# lcdconnector3.net
KiCad netlist of a schematic drawn in EAGLE
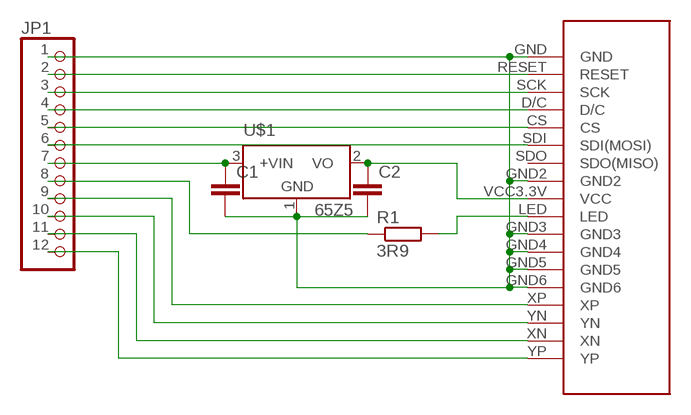
[diagram p0: schematic, sheet 1]

(export (version "E")
  (design (tool "Eeschema 10.0.6"))
  (components
    (comp (ref "C1")
      (value "C-EUC0805")
      (footprint "eagle-import:C0805")
      (libsource (lib "eagle-import") (part "C-EUC0805"))
    )
    (comp (ref "C2")
      (value "C-EUC0805")
      (footprint "eagle-import:C0805")
      (libsource (lib "eagle-import") (part "C-EUC0805"))
    )
    (comp (ref "CONNECTOR1")
      (value "TJCTM24024-PINS")
      (footprint "eagle-import:TJCTM24024-PINS")
      (libsource (lib "eagle-import") (part "TJCTM24024-PINS"))
    )
    (comp (ref "JP1")
      (value "PINHD-1X12-CB")
      (footprint "eagle-import:1X12-CB")
      (libsource (lib "eagle-import") (part "PINHD-1X12-CB"))
    )
    (comp (ref "R1")
      (value "3R9")
      (footprint "eagle-import:R0805")
      (libsource (lib "eagle-import") (part "R-EU_R0805"))
    )
    (comp (ref "U$1")
      (value "65Z5")
      (footprint "eagle-import:SOT23")
      (libsource (lib "eagle-import") (part "65Z5"))
    )
  )
  (nets
    (net (code "1") (name "Net-(CONNECTOR1-PadCS)") (class "Default")
      (node (ref "CONNECTOR1") (pin "CS") (pinfunction "CS_CS") (pintype "bidirectional"))
      (node (ref "JP1") (pin "5") (pinfunction "5_5") (pintype "passive"))
    )
    (net (code "2") (name "Net-(CONNECTOR1-PadD{slash}C)") (class "Default")
      (node (ref "CONNECTOR1") (pin "D/C") (pinfunction "D/C_D/C") (pintype "bidirectional"))
      (node (ref "JP1") (pin "4") (pinfunction "4_4") (pintype "passive"))
    )
    (net (code "3") (name "Net-(CONNECTOR1-PadLED)") (class "Default")
      (node (ref "CONNECTOR1") (pin "LED") (pinfunction "LED_LED") (pintype "bidirectional"))
      (node (ref "R1") (pin "2") (pinfunction "2_2") (pintype "passive"))
    )
    (net (code "4") (name "Net-(CONNECTOR1-PadRESET)") (class "Default")
      (node (ref "CONNECTOR1") (pin "RESET") (pinfunction "RESET_RESET") (pintype "bidirectional"))
      (node (ref "JP1") (pin "2") (pinfunction "2_2") (pintype "passive"))
    )
    (net (code "5") (name "Net-(CONNECTOR1-PadSCK)") (class "Default")
      (node (ref "CONNECTOR1") (pin "SCK") (pinfunction "SCK_SCK") (pintype "bidirectional"))
      (node (ref "JP1") (pin "3") (pinfunction "3_3") (pintype "passive"))
    )
    (net (code "6") (name "Net-(CONNECTOR1-PadXN)") (class "Default")
      (node (ref "CONNECTOR1") (pin "XN") (pinfunction "XN_XN") (pintype "bidirectional"))
      (node (ref "JP1") (pin "11") (pinfunction "11_11") (pintype "passive"))
    )
    (net (code "7") (name "Net-(CONNECTOR1-PadXP)") (class "Default")
      (node (ref "CONNECTOR1") (pin "XP") (pinfunction "XP_XP") (pintype "bidirectional"))
      (node (ref "JP1") (pin "9") (pinfunction "9_9") (pintype "passive"))
    )
    (net (code "8") (name "Net-(CONNECTOR1-PadYN)") (class "Default")
      (node (ref "CONNECTOR1") (pin "YN") (pinfunction "YN_YN") (pintype "bidirectional"))
      (node (ref "JP1") (pin "10") (pinfunction "10_10") (pintype "passive"))
    )
    (net (code "9") (name "Net-(CONNECTOR1-PadYP)") (class "Default")
      (node (ref "CONNECTOR1") (pin "YP") (pinfunction "YP_YP") (pintype "bidirectional"))
      (node (ref "JP1") (pin "12") (pinfunction "12_12") (pintype "passive"))
    )
    (net (code "10") (name "Net-(CONNECTOR1-SDI(MOSI))") (class "Default")
      (node (ref "CONNECTOR1") (pin "SDI") (pinfunction "SDI(MOSI)_SDI") (pintype "bidirectional"))
      (node (ref "JP1") (pin "6") (pinfunction "6_6") (pintype "passive"))
    )
    (net (code "11") (name "Net-(CONNECTOR1-VCC)") (class "Default")
      (node (ref "C2") (pin "1") (pinfunction "1_1") (pintype "passive"))
      (node (ref "CONNECTOR1") (pin "VCC3.3V") (pinfunction "VCC_VCC3.3V") (pintype "bidirectional"))
      (node (ref "U$1") (pin "2") (pinfunction "VO_2") (pintype "input"))
    )
    (net (code "12") (name "Net-(JP1-Pad8)") (class "Default")
      (node (ref "JP1") (pin "8") (pinfunction "8_8") (pintype "passive"))
      (node (ref "R1") (pin "1") (pinfunction "1_1") (pintype "passive"))
    )
    (net (code "13") (name "Net-(U$1-+VIN)") (class "Default")
      (node (ref "C1") (pin "1") (pinfunction "1_1") (pintype "passive"))
      (node (ref "JP1") (pin "7") (pinfunction "7_7") (pintype "passive"))
      (node (ref "U$1") (pin "3") (pinfunction "+VIN_3") (pintype "input"))
    )
    (net (code "14") (name "Net-(U$1-GND)") (class "Default")
      (node (ref "C1") (pin "2") (pinfunction "2_2") (pintype "passive"))
      (node (ref "C2") (pin "2") (pinfunction "2_2") (pintype "passive"))
      (node (ref "CONNECTOR1") (pin "GND") (pinfunction "GND_GND") (pintype "bidirectional"))
      (node (ref "CONNECTOR1") (pin "GND2") (pinfunction "GND2_GND2") (pintype "bidirectional"))
      (node (ref "CONNECTOR1") (pin "GND3") (pinfunction "GND3_GND3") (pintype "bidirectional"))
      (node (ref "CONNECTOR1") (pin "GND4") (pinfunction "GND4_GND4") (pintype "bidirectional"))
      (node (ref "CONNECTOR1") (pin "GND5") (pinfunction "GND5_GND5") (pintype "bidirectional"))
      (node (ref "CONNECTOR1") (pin "GND6") (pinfunction "GND6_GND6") (pintype "bidirectional"))
      (node (ref "JP1") (pin "1") (pinfunction "1_1") (pintype "passive"))
      (node (ref "U$1") (pin "1") (pinfunction "GND_1") (pintype "power_in"))
    )
    (net (code "15") (name "unconnected-(CONNECTOR1-SDO(MISO)-PadSDO)") (class "Default")
      (node (ref "CONNECTOR1") (pin "SDO") (pinfunction "SDO(MISO)_SDO") (pintype "bidirectional"))
    )
  )
)
